# M709X.net
KiCad netlist of a schematic drawn in EAGLE
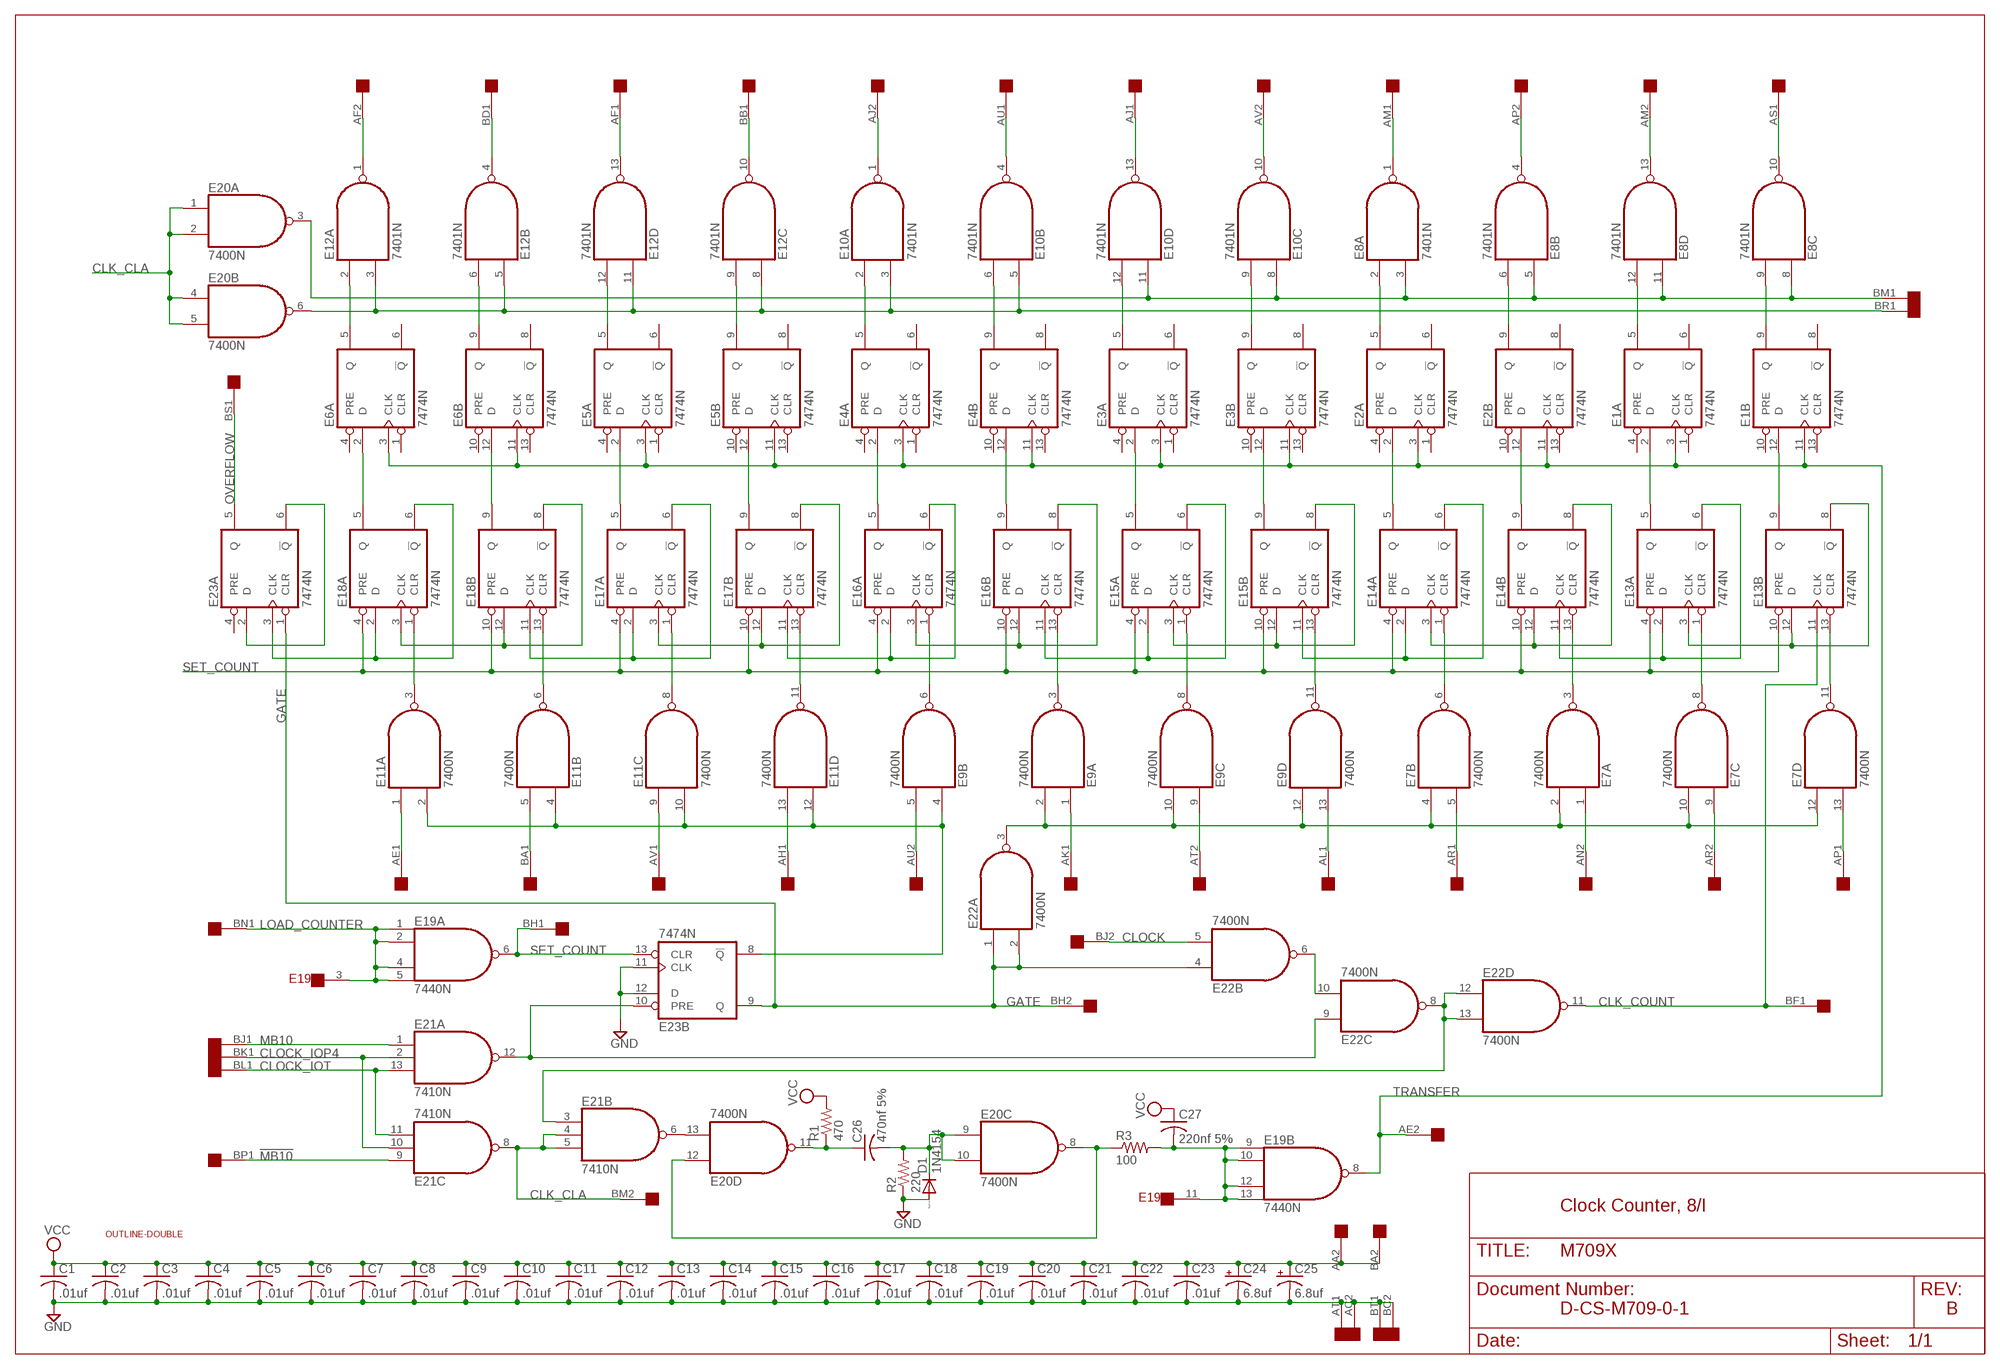
[diagram p0: schematic, sheet 1]

(export (version "E")
  (design (tool "Eeschema 10.0.6"))
  (components
    (comp (ref "C1")
      (value ".01uf")
      (footprint "eagle-import:C075-032X103")
      (libsource (lib "eagle-import") (part "C-US075-032X103"))
    )
    (comp (ref "C2")
      (value ".01uf")
      (footprint "eagle-import:C075-032X103")
      (libsource (lib "eagle-import") (part "C-US075-032X103"))
    )
    (comp (ref "C3")
      (value ".01uf")
      (footprint "eagle-import:C075-032X103")
      (libsource (lib "eagle-import") (part "C-US075-032X103"))
    )
    (comp (ref "C4")
      (value ".01uf")
      (footprint "eagle-import:C075-032X103")
      (libsource (lib "eagle-import") (part "C-US075-032X103"))
    )
    (comp (ref "C5")
      (value ".01uf")
      (footprint "eagle-import:C075-032X103")
      (libsource (lib "eagle-import") (part "C-US075-032X103"))
    )
    (comp (ref "C6")
      (value ".01uf")
      (footprint "eagle-import:C075-032X103")
      (libsource (lib "eagle-import") (part "C-US075-032X103"))
    )
    (comp (ref "C7")
      (value ".01uf")
      (footprint "eagle-import:C075-032X103")
      (libsource (lib "eagle-import") (part "C-US075-032X103"))
    )
    (comp (ref "C8")
      (value ".01uf")
      (footprint "eagle-import:C075-032X103")
      (libsource (lib "eagle-import") (part "C-US075-032X103"))
    )
    (comp (ref "C9")
      (value ".01uf")
      (footprint "eagle-import:C075-032X103")
      (libsource (lib "eagle-import") (part "C-US075-032X103"))
    )
    (comp (ref "C10")
      (value ".01uf")
      (footprint "eagle-import:C075-032X103")
      (libsource (lib "eagle-import") (part "C-US075-032X103"))
    )
    (comp (ref "C11")
      (value ".01uf")
      (footprint "eagle-import:C075-032X103")
      (libsource (lib "eagle-import") (part "C-US075-032X103"))
    )
    (comp (ref "C12")
      (value ".01uf")
      (footprint "eagle-import:C075-032X103")
      (libsource (lib "eagle-import") (part "C-US075-032X103"))
    )
    (comp (ref "C13")
      (value ".01uf")
      (footprint "eagle-import:C075-032X103")
      (libsource (lib "eagle-import") (part "C-US075-032X103"))
    )
    (comp (ref "C14")
      (value ".01uf")
      (footprint "eagle-import:C075-032X103")
      (libsource (lib "eagle-import") (part "C-US075-032X103"))
    )
    (comp (ref "C15")
      (value ".01uf")
      (footprint "eagle-import:C075-032X103")
      (libsource (lib "eagle-import") (part "C-US075-032X103"))
    )
    (comp (ref "C16")
      (value ".01uf")
      (footprint "eagle-import:C075-032X103")
      (libsource (lib "eagle-import") (part "C-US075-032X103"))
    )
    (comp (ref "C17")
      (value ".01uf")
      (footprint "eagle-import:C075-032X103")
      (libsource (lib "eagle-import") (part "C-US075-032X103"))
    )
    (comp (ref "C18")
      (value ".01uf")
      (footprint "eagle-import:C075-032X103")
      (libsource (lib "eagle-import") (part "C-US075-032X103"))
    )
    (comp (ref "C19")
      (value ".01uf")
      (footprint "eagle-import:C075-032X103")
      (libsource (lib "eagle-import") (part "C-US075-032X103"))
    )
    (comp (ref "C20")
      (value ".01uf")
      (footprint "eagle-import:C075-032X103")
      (libsource (lib "eagle-import") (part "C-US075-032X103"))
    )
    (comp (ref "C21")
      (value ".01uf")
      (footprint "eagle-import:C075-032X103")
      (libsource (lib "eagle-import") (part "C-US075-032X103"))
    )
    (comp (ref "C22")
      (value ".01uf")
      (footprint "eagle-import:C075-032X103")
      (libsource (lib "eagle-import") (part "C-US075-032X103"))
    )
    (comp (ref "C23")
      (value ".01uf")
      (footprint "eagle-import:C075-032X103")
      (libsource (lib "eagle-import") (part "C-US075-032X103"))
    )
    (comp (ref "C24")
      (value "6.8uf")
      (footprint "eagle-import:E15-5")
      (libsource (lib "eagle-import") (part "CPOL-USE15-5AXIAL"))
    )
    (comp (ref "C25")
      (value "6.8uf")
      (footprint "eagle-import:E15-5")
      (libsource (lib "eagle-import") (part "CPOL-USE15-5AXIAL"))
    )
    (comp (ref "C26")
      (value "470nf 5%")
      (footprint "eagle-import:C075-032X103")
      (libsource (lib "eagle-import") (part "C-US075-032X103"))
    )
    (comp (ref "C27")
      (value "220nf 5%")
      (footprint "eagle-import:C075-032X103")
      (libsource (lib "eagle-import") (part "C-US075-032X103"))
    )
    (comp (ref "D1")
      (value "1N4154")
      (footprint "eagle-import:SOD61B")
      (libsource (lib "eagle-import") (part "DIODE-SOD61B"))
    )
    (comp (ref "E1")
      (value "7474N")
      (footprint "eagle-import:DIL14")
      (libsource (lib "eagle-import") (part "7474NS"))
    )
    (comp (ref "E2")
      (value "7474N")
      (footprint "eagle-import:DIL14")
      (libsource (lib "eagle-import") (part "7474NS"))
    )
    (comp (ref "E3")
      (value "7474N")
      (footprint "eagle-import:DIL14")
      (libsource (lib "eagle-import") (part "7474NS"))
    )
    (comp (ref "E4")
      (value "7474N")
      (footprint "eagle-import:DIL14")
      (libsource (lib "eagle-import") (part "7474NS"))
    )
    (comp (ref "E5")
      (value "7474N")
      (footprint "eagle-import:DIL14")
      (libsource (lib "eagle-import") (part "7474NS"))
    )
    (comp (ref "E6")
      (value "7474N")
      (footprint "eagle-import:DIL14")
      (libsource (lib "eagle-import") (part "7474NS"))
    )
    (comp (ref "E7")
      (value "7400N")
      (footprint "eagle-import:DIL14")
      (libsource (lib "eagle-import") (part "7400N"))
    )
    (comp (ref "E8")
      (value "7401N")
      (footprint "eagle-import:DIL14")
      (libsource (lib "eagle-import") (part "7401NLS"))
    )
    (comp (ref "E9")
      (value "7400N")
      (footprint "eagle-import:DIL14")
      (libsource (lib "eagle-import") (part "7400N"))
    )
    (comp (ref "E10")
      (value "7401N")
      (footprint "eagle-import:DIL14")
      (libsource (lib "eagle-import") (part "7401NLS"))
    )
    (comp (ref "E11")
      (value "7400N")
      (footprint "eagle-import:DIL14")
      (libsource (lib "eagle-import") (part "7400N"))
    )
    (comp (ref "E12")
      (value "7401N")
      (footprint "eagle-import:DIL14")
      (libsource (lib "eagle-import") (part "7401NLS"))
    )
    (comp (ref "E13")
      (value "7474N")
      (footprint "eagle-import:DIL14")
      (libsource (lib "eagle-import") (part "7474NS"))
    )
    (comp (ref "E14")
      (value "7474N")
      (footprint "eagle-import:DIL14")
      (libsource (lib "eagle-import") (part "7474NS"))
    )
    (comp (ref "E15")
      (value "7474N")
      (footprint "eagle-import:DIL14")
      (libsource (lib "eagle-import") (part "7474NS"))
    )
    (comp (ref "E16")
      (value "7474N")
      (footprint "eagle-import:DIL14")
      (libsource (lib "eagle-import") (part "7474NS"))
    )
    (comp (ref "E17")
      (value "7474N")
      (footprint "eagle-import:DIL14")
      (libsource (lib "eagle-import") (part "7474NS"))
    )
    (comp (ref "E18")
      (value "7474N")
      (footprint "eagle-import:DIL14")
      (libsource (lib "eagle-import") (part "7474NS"))
    )
    (comp (ref "E19")
      (value "7440N")
      (footprint "eagle-import:DIL14")
      (libsource (lib "eagle-import") (part "7440NS"))
    )
    (comp (ref "E20")
      (value "7400N")
      (footprint "eagle-import:DIL14")
      (libsource (lib "eagle-import") (part "7400N"))
    )
    (comp (ref "E21")
      (value "7410N")
      (footprint "eagle-import:DIL14")
      (libsource (lib "eagle-import") (part "7410N"))
    )
    (comp (ref "E22")
      (value "7400N")
      (footprint "eagle-import:DIL14")
      (libsource (lib "eagle-import") (part "7400N"))
    )
    (comp (ref "E23")
      (value "7474N")
      (footprint "eagle-import:DIL14")
      (libsource (lib "eagle-import") (part "7474NS"))
    )
    (comp (ref "R1")
      (value "470")
      (footprint "eagle-import:0207_15")
      (libsource (lib "eagle-import") (part "R-US_0207/15"))
    )
    (comp (ref "R2")
      (value "220")
      (footprint "eagle-import:0207_15")
      (libsource (lib "eagle-import") (part "R-US_0207/15"))
    )
    (comp (ref "R3")
      (value "100")
      (footprint "eagle-import:0207_15")
      (libsource (lib "eagle-import") (part "R-US_0207/15"))
    )
    (comp (ref "U$1")
      (value "OUTLINE-DOUBLE")
      (footprint "eagle-import:DOUBLE")
      (libsource (lib "eagle-import") (part "OUTLINE-DOUBLE"))
    )
    (comp (ref "U$2")
      (value "DOUBLE")
      (footprint "eagle-import:EDGE-CON4")
      (libsource (lib "eagle-import") (part "DOUBLE"))
    )
  )
  (nets
    (net (code "1") (name "/CLK_CLA") (class "Default")
      (node (ref "E20") (pin "1") (pinfunction "I0_1") (pintype "input"))
      (node (ref "E20") (pin "2") (pinfunction "I1_2") (pintype "input"))
      (node (ref "E20") (pin "4") (pinfunction "I0_4") (pintype "input"))
      (node (ref "E20") (pin "5") (pinfunction "I1_5") (pintype "input"))
      (node (ref "E21") (pin "4") (pinfunction "I1_4") (pintype "input"))
      (node (ref "E21") (pin "5") (pinfunction "I2_5") (pintype "input"))
      (node (ref "E21") (pin "8") (pinfunction "O_8") (pintype "output"))
      (node (ref "U$2") (pin "BM2") (pinfunction "1_BM2") (pintype "bidirectional"))
    )
    (net (code "2") (name "/CLK_COUNT") (class "Default")
      (node (ref "E13") (pin "11") (pinfunction "CLK_11") (pintype "input"))
      (node (ref "E22") (pin "11") (pinfunction "O_11") (pintype "output"))
      (node (ref "U$2") (pin "BF1") (pinfunction "1_BF1") (pintype "bidirectional"))
    )
    (net (code "3") (name "/CLOCK") (class "Default")
      (node (ref "E22") (pin "5") (pinfunction "I1_5") (pintype "input"))
      (node (ref "U$2") (pin "BJ2") (pinfunction "1_BJ2") (pintype "bidirectional"))
    )
    (net (code "4") (name "/CLOCK_IOP4") (class "Default")
      (node (ref "E21") (pin "10") (pinfunction "I1_10") (pintype "input"))
      (node (ref "E21") (pin "2") (pinfunction "I1_2") (pintype "input"))
      (node (ref "U$2") (pin "BK1") (pinfunction "1_BK1") (pintype "bidirectional"))
    )
    (net (code "5") (name "/CLOCK_IOT") (class "Default")
      (node (ref "E21") (pin "11") (pinfunction "I2_11") (pintype "input"))
      (node (ref "E21") (pin "13") (pinfunction "I2_13") (pintype "input"))
      (node (ref "U$2") (pin "BL1") (pinfunction "1_BL1") (pintype "bidirectional"))
    )
    (net (code "6") (name "/GATE") (class "Default")
      (node (ref "E22") (pin "1") (pinfunction "I0_1") (pintype "input"))
      (node (ref "E22") (pin "2") (pinfunction "I1_2") (pintype "input"))
      (node (ref "E22") (pin "4") (pinfunction "I0_4") (pintype "input"))
      (node (ref "E23") (pin "1") (pinfunction "CLR_1") (pintype "input"))
      (node (ref "E23") (pin "9") (pinfunction "Q_9") (pintype "output"))
      (node (ref "U$2") (pin "BH2") (pinfunction "1_BH2") (pintype "bidirectional"))
    )
    (net (code "7") (name "/LOAD_COUNTER") (class "Default")
      (node (ref "E19") (pin "1") (pinfunction "I0_1") (pintype "input"))
      (node (ref "E19") (pin "2") (pinfunction "I1_2") (pintype "input"))
      (node (ref "E19") (pin "3") (pinfunction "NC_3") (pintype "passive"))
      (node (ref "E19") (pin "4") (pinfunction "I2_4") (pintype "input"))
      (node (ref "E19") (pin "5") (pinfunction "I3_5") (pintype "input"))
      (node (ref "U$2") (pin "BN1") (pinfunction "1_BN1") (pintype "bidirectional"))
    )
    (net (code "8") (name "/MB10") (class "Default")
      (node (ref "E21") (pin "1") (pinfunction "I0_1") (pintype "input"))
      (node (ref "U$2") (pin "BJ1") (pinfunction "1_BJ1") (pintype "bidirectional"))
    )
    (net (code "9") (name "/OVERFLOW") (class "Default")
      (node (ref "E23") (pin "5") (pinfunction "Q_5") (pintype "output"))
      (node (ref "U$2") (pin "BS1") (pinfunction "1_BS1") (pintype "bidirectional"))
    )
    (net (code "10") (name "/SET_COUNT") (class "Default")
      (node (ref "E13") (pin "10") (pinfunction "PRE_10") (pintype "input"))
      (node (ref "E13") (pin "4") (pinfunction "PRE_4") (pintype "input"))
      (node (ref "E14") (pin "10") (pinfunction "PRE_10") (pintype "input"))
      (node (ref "E14") (pin "4") (pinfunction "PRE_4") (pintype "input"))
      (node (ref "E15") (pin "10") (pinfunction "PRE_10") (pintype "input"))
      (node (ref "E15") (pin "4") (pinfunction "PRE_4") (pintype "input"))
      (node (ref "E16") (pin "10") (pinfunction "PRE_10") (pintype "input"))
      (node (ref "E16") (pin "4") (pinfunction "PRE_4") (pintype "input"))
      (node (ref "E17") (pin "10") (pinfunction "PRE_10") (pintype "input"))
      (node (ref "E17") (pin "4") (pinfunction "PRE_4") (pintype "input"))
      (node (ref "E18") (pin "10") (pinfunction "PRE_10") (pintype "input"))
      (node (ref "E18") (pin "4") (pinfunction "PRE_4") (pintype "input"))
      (node (ref "E19") (pin "6") (pinfunction "O_6") (pintype "output"))
      (node (ref "E23") (pin "13") (pinfunction "CLR_13") (pintype "input"))
      (node (ref "U$2") (pin "BH1") (pinfunction "1_BH1") (pintype "bidirectional"))
    )
    (net (code "11") (name "/TRANSFER") (class "Default")
      (node (ref "E1") (pin "11") (pinfunction "CLK_11") (pintype "input"))
      (node (ref "E1") (pin "3") (pinfunction "CLK_3") (pintype "input"))
      (node (ref "E19") (pin "8") (pinfunction "O_8") (pintype "output"))
      (node (ref "E2") (pin "11") (pinfunction "CLK_11") (pintype "input"))
      (node (ref "E2") (pin "3") (pinfunction "CLK_3") (pintype "input"))
      (node (ref "E3") (pin "11") (pinfunction "CLK_11") (pintype "input"))
      (node (ref "E3") (pin "3") (pinfunction "CLK_3") (pintype "input"))
      (node (ref "E4") (pin "11") (pinfunction "CLK_11") (pintype "input"))
      (node (ref "E4") (pin "3") (pinfunction "CLK_3") (pintype "input"))
      (node (ref "E5") (pin "11") (pinfunction "CLK_11") (pintype "input"))
      (node (ref "E5") (pin "3") (pinfunction "CLK_3") (pintype "input"))
      (node (ref "E6") (pin "11") (pinfunction "CLK_11") (pintype "input"))
      (node (ref "E6") (pin "3") (pinfunction "CLK_3") (pintype "input"))
      (node (ref "U$2") (pin "AE2") (pinfunction "1_AE2") (pintype "bidirectional"))
    )
    (net (code "12") (name "/~{MB10}") (class "Default")
      (node (ref "E21") (pin "9") (pinfunction "I0_9") (pintype "input"))
      (node (ref "U$2") (pin "BP1") (pinfunction "1_BP1") (pintype "bidirectional"))
    )
    (net (code "13") (name "GND") (class "Default")
      (node (ref "C1") (pin "2") (pinfunction "2_2") (pintype "passive"))
      (node (ref "C10") (pin "2") (pinfunction "2_2") (pintype "passive"))
      (node (ref "C11") (pin "2") (pinfunction "2_2") (pintype "passive"))
      (node (ref "C12") (pin "2") (pinfunction "2_2") (pintype "passive"))
      (node (ref "C13") (pin "2") (pinfunction "2_2") (pintype "passive"))
      (node (ref "C14") (pin "2") (pinfunction "2_2") (pintype "passive"))
      (node (ref "C15") (pin "2") (pinfunction "2_2") (pintype "passive"))
      (node (ref "C16") (pin "2") (pinfunction "2_2") (pintype "passive"))
      (node (ref "C17") (pin "2") (pinfunction "2_2") (pintype "passive"))
      (node (ref "C18") (pin "2") (pinfunction "2_2") (pintype "passive"))
      (node (ref "C19") (pin "2") (pinfunction "2_2") (pintype "passive"))
      (node (ref "C2") (pin "2") (pinfunction "2_2") (pintype "passive"))
      (node (ref "C20") (pin "2") (pinfunction "2_2") (pintype "passive"))
      (node (ref "C21") (pin "2") (pinfunction "2_2") (pintype "passive"))
      (node (ref "C22") (pin "2") (pinfunction "2_2") (pintype "passive"))
      (node (ref "C23") (pin "2") (pinfunction "2_2") (pintype "passive"))
      (node (ref "C24") (pin "-") (pinfunction "-_-") (pintype "passive"))
      (node (ref "C25") (pin "-") (pinfunction "-_-") (pintype "passive"))
      (node (ref "C3") (pin "2") (pinfunction "2_2") (pintype "passive"))
      (node (ref "C4") (pin "2") (pinfunction "2_2") (pintype "passive"))
      (node (ref "C5") (pin "2") (pinfunction "2_2") (pintype "passive"))
      (node (ref "C6") (pin "2") (pinfunction "2_2") (pintype "passive"))
      (node (ref "C7") (pin "2") (pinfunction "2_2") (pintype "passive"))
      (node (ref "C8") (pin "2") (pinfunction "2_2") (pintype "passive"))
      (node (ref "C9") (pin "2") (pinfunction "2_2") (pintype "passive"))
      (node (ref "D1") (pin "A") (pinfunction "A_A") (pintype "passive"))
      (node (ref "E23") (pin "11") (pinfunction "CLK_11") (pintype "input"))
      (node (ref "E23") (pin "12") (pinfunction "D_12") (pintype "input"))
      (node (ref "R2") (pin "1") (pinfunction "1_1") (pintype "passive"))
      (node (ref "U$2") (pin "AC2") (pinfunction "1_AC2") (pintype "bidirectional"))
      (node (ref "U$2") (pin "AT1") (pinfunction "1_AT1") (pintype "bidirectional"))
      (node (ref "U$2") (pin "BC2") (pinfunction "1_BC2") (pintype "bidirectional"))
      (node (ref "U$2") (pin "BT1") (pinfunction "1_BT1") (pintype "bidirectional"))
    )
    (net (code "14") (name "Net-(E1A-Q)") (class "Default")
      (node (ref "E1") (pin "5") (pinfunction "Q_5") (pintype "output"))
      (node (ref "E8") (pin "12") (pinfunction "I1_12") (pintype "input"))
    )
    (net (code "15") (name "Net-(E1B-Q)") (class "Default")
      (node (ref "E1") (pin "9") (pinfunction "Q_9") (pintype "output"))
      (node (ref "E8") (pin "9") (pinfunction "I1_9") (pintype "input"))
    )
    (net (code "16") (name "Net-(E2A-Q)") (class "Default")
      (node (ref "E2") (pin "5") (pinfunction "Q_5") (pintype "output"))
      (node (ref "E8") (pin "2") (pinfunction "I0_2") (pintype "input"))
    )
    (net (code "17") (name "Net-(E2B-Q)") (class "Default")
      (node (ref "E2") (pin "9") (pinfunction "Q_9") (pintype "output"))
      (node (ref "E8") (pin "6") (pinfunction "I1_6") (pintype "input"))
    )
    (net (code "18") (name "Net-(E7A-I0)") (class "Default")
      (node (ref "E7") (pin "1") (pinfunction "I0_1") (pintype "input"))
      (node (ref "U$2") (pin "AN2") (pinfunction "1_AN2") (pintype "bidirectional"))
    )
    (net (code "19") (name "Net-(E7B-I1)") (class "Default")
      (node (ref "E7") (pin "5") (pinfunction "I1_5") (pintype "input"))
      (node (ref "U$2") (pin "AR1") (pinfunction "1_AR1") (pintype "bidirectional"))
    )
    (net (code "20") (name "Net-(E7C-I0)") (class "Default")
      (node (ref "E7") (pin "9") (pinfunction "I0_9") (pintype "input"))
      (node (ref "U$2") (pin "AR2") (pinfunction "1_AR2") (pintype "bidirectional"))
    )
    (net (code "21") (name "Net-(E7D-I1)") (class "Default")
      (node (ref "E7") (pin "13") (pinfunction "I1_13") (pintype "input"))
      (node (ref "U$2") (pin "AP1") (pinfunction "1_AP1") (pintype "bidirectional"))
    )
    (net (code "22") (name "Net-(E8A-O)") (class "Default")
      (node (ref "E8") (pin "1") (pinfunction "O_1") (pintype "open_collector"))
      (node (ref "U$2") (pin "AM1") (pinfunction "1_AM1") (pintype "bidirectional"))
    )
    (net (code "23") (name "Net-(E8B-O)") (class "Default")
      (node (ref "E8") (pin "4") (pinfunction "O_4") (pintype "open_collector"))
      (node (ref "U$2") (pin "AP2") (pinfunction "1_AP2") (pintype "bidirectional"))
    )
    (net (code "24") (name "Net-(E8C-O)") (class "Default")
      (node (ref "E8") (pin "10") (pinfunction "O_10") (pintype "open_collector"))
      (node (ref "U$2") (pin "AS1") (pinfunction "1_AS1") (pintype "bidirectional"))
    )
    (net (code "25") (name "Net-(E8D-O)") (class "Default")
      (node (ref "E8") (pin "13") (pinfunction "O_13") (pintype "open_collector"))
      (node (ref "U$2") (pin "AM2") (pinfunction "1_AM2") (pintype "bidirectional"))
    )
    (net (code "26") (name "Net-(E9A-I0)") (class "Default")
      (node (ref "E9") (pin "1") (pinfunction "I0_1") (pintype "input"))
      (node (ref "U$2") (pin "AK1") (pinfunction "1_AK1") (pintype "bidirectional"))
    )
    (net (code "27") (name "Net-(E9B-I1)") (class "Default")
      (node (ref "E9") (pin "5") (pinfunction "I1_5") (pintype "input"))
      (node (ref "U$2") (pin "AU2") (pinfunction "1_AU2") (pintype "bidirectional"))
    )
    (net (code "28") (name "Net-(E9C-I0)") (class "Default")
      (node (ref "E9") (pin "9") (pinfunction "I0_9") (pintype "input"))
      (node (ref "U$2") (pin "AT2") (pinfunction "1_AT2") (pintype "bidirectional"))
    )
    (net (code "29") (name "Net-(E9D-I1)") (class "Default")
      (node (ref "E9") (pin "13") (pinfunction "I1_13") (pintype "input"))
      (node (ref "U$2") (pin "AL1") (pinfunction "1_AL1") (pintype "bidirectional"))
    )
    (net (code "30") (name "Net-(E10A-I0)") (class "Default")
      (node (ref "E10") (pin "2") (pinfunction "I0_2") (pintype "input"))
      (node (ref "E4") (pin "5") (pinfunction "Q_5") (pintype "output"))
    )
    (net (code "31") (name "Net-(E10A-I1)") (class "Default")
      (node (ref "E10") (pin "3") (pinfunction "I1_3") (pintype "input"))
      (node (ref "E10") (pin "5") (pinfunction "I0_5") (pintype "input"))
      (node (ref "E12") (pin "11") (pinfunction "I0_11") (pintype "input"))
      (node (ref "E12") (pin "3") (pinfunction "I1_3") (pintype "input"))
      (node (ref "E12") (pin "5") (pinfunction "I0_5") (pintype "input"))
      (node (ref "E12") (pin "8") (pinfunction "I0_8") (pintype "input"))
      (node (ref "E20") (pin "6") (pinfunction "O_6") (pintype "output"))
      (node (ref "U$2") (pin "BR1") (pinfunction "1_BR1") (pintype "bidirectional"))
    )
    (net (code "32") (name "Net-(E10A-O)") (class "Default")
      (node (ref "E10") (pin "1") (pinfunction "O_1") (pintype "open_collector"))
      (node (ref "U$2") (pin "AJ2") (pinfunction "1_AJ2") (pintype "bidirectional"))
    )
    (net (code "33") (name "Net-(E10B-I1)") (class "Default")
      (node (ref "E10") (pin "6") (pinfunction "I1_6") (pintype "input"))
      (node (ref "E4") (pin "9") (pinfunction "Q_9") (pintype "output"))
    )
    (net (code "34") (name "Net-(E10B-O)") (class "Default")
      (node (ref "E10") (pin "4") (pinfunction "O_4") (pintype "open_collector"))
      (node (ref "U$2") (pin "AU1") (pinfunction "1_AU1") (pintype "bidirectional"))
    )
    (net (code "35") (name "Net-(E10C-I0)") (class "Default")
      (node (ref "E10") (pin "11") (pinfunction "I0_11") (pintype "input"))
      (node (ref "E10") (pin "8") (pinfunction "I0_8") (pintype "input"))
      (node (ref "E20") (pin "3") (pinfunction "O_3") (pintype "output"))
      (node (ref "E8") (pin "11") (pinfunction "I0_11") (pintype "input"))
      (node (ref "E8") (pin "3") (pinfunction "I1_3") (pintype "input"))
      (node (ref "E8") (pin "5") (pinfunction "I0_5") (pintype "input"))
      (node (ref "E8") (pin "8") (pinfunction "I0_8") (pintype "input"))
      (node (ref "U$2") (pin "BM1") (pinfunction "1_BM1") (pintype "bidirectional"))
    )
    (net (code "36") (name "Net-(E10C-I1)") (class "Default")
      (node (ref "E10") (pin "9") (pinfunction "I1_9") (pintype "input"))
      (node (ref "E3") (pin "9") (pinfunction "Q_9") (pintype "output"))
    )
    (net (code "37") (name "Net-(E10C-O)") (class "Default")
      (node (ref "E10") (pin "10") (pinfunction "O_10") (pintype "open_collector"))
      (node (ref "U$2") (pin "AV2") (pinfunction "1_AV2") (pintype "bidirectional"))
    )
    (net (code "38") (name "Net-(E10D-I1)") (class "Default")
      (node (ref "E10") (pin "12") (pinfunction "I1_12") (pintype "input"))
      (node (ref "E3") (pin "5") (pinfunction "Q_5") (pintype "output"))
    )
    (net (code "39") (name "Net-(E10D-O)") (class "Default")
      (node (ref "E10") (pin "13") (pinfunction "O_13") (pintype "open_collector"))
      (node (ref "U$2") (pin "AJ1") (pinfunction "1_AJ1") (pintype "bidirectional"))
    )
    (net (code "40") (name "Net-(E11A-I0)") (class "Default")
      (node (ref "E11") (pin "1") (pinfunction "I0_1") (pintype "input"))
      (node (ref "U$2") (pin "AE1") (pinfunction "1_AE1") (pintype "bidirectional"))
    )
    (net (code "41") (name "Net-(E11A-I1)") (class "Default")
      (node (ref "E11") (pin "10") (pinfunction "I1_10") (pintype "input"))
      (node (ref "E11") (pin "12") (pinfunction "I0_12") (pintype "input"))
      (node (ref "E11") (pin "2") (pinfunction "I1_2") (pintype "input"))
      (node (ref "E11") (pin "4") (pinfunction "I0_4") (pintype "input"))
      (node (ref "E23") (pin "8") (pinfunction "~{Q}_8") (pintype "output"))
      (node (ref "E9") (pin "4") (pinfunction "I0_4") (pintype "input"))
    )
    (net (code "42") (name "Net-(E11A-O)") (class "Default")
      (node (ref "E11") (pin "3") (pinfunction "O_3") (pintype "output"))
      (node (ref "E18") (pin "1") (pinfunction "CLR_1") (pintype "input"))
    )
    (net (code "43") (name "Net-(E11B-I1)") (class "Default")
      (node (ref "E11") (pin "5") (pinfunction "I1_5") (pintype "input"))
      (node (ref "U$2") (pin "BA1") (pinfunction "1_BA1") (pintype "bidirectional"))
    )
    (net (code "44") (name "Net-(E11B-O)") (class "Default")
      (node (ref "E11") (pin "6") (pinfunction "O_6") (pintype "output"))
      (node (ref "E18") (pin "13") (pinfunction "CLR_13") (pintype "input"))
    )
    (net (code "45") (name "Net-(E11C-I0)") (class "Default")
      (node (ref "E11") (pin "9") (pinfunction "I0_9") (pintype "input"))
      (node (ref "U$2") (pin "AV1") (pinfunction "1_AV1") (pintype "bidirectional"))
    )
    (net (code "46") (name "Net-(E11C-O)") (class "Default")
      (node (ref "E11") (pin "8") (pinfunction "O_8") (pintype "output"))
      (node (ref "E17") (pin "1") (pinfunction "CLR_1") (pintype "input"))
    )
    (net (code "47") (name "Net-(E11D-I1)") (class "Default")
      (node (ref "E11") (pin "13") (pinfunction "I1_13") (pintype "input"))
      (node (ref "U$2") (pin "AH1") (pinfunction "1_AH1") (pintype "bidirectional"))
    )
    (net (code "48") (name "Net-(E11D-O)") (class "Default")
      (node (ref "E11") (pin "11") (pinfunction "O_11") (pintype "output"))
      (node (ref "E17") (pin "13") (pinfunction "CLR_13") (pintype "input"))
    )
    (net (code "49") (name "Net-(E12A-I0)") (class "Default")
      (node (ref "E12") (pin "2") (pinfunction "I0_2") (pintype "input"))
      (node (ref "E6") (pin "5") (pinfunction "Q_5") (pintype "output"))
    )
    (net (code "50") (name "Net-(E12A-O)") (class "Default")
      (node (ref "E12") (pin "1") (pinfunction "O_1") (pintype "open_collector"))
      (node (ref "U$2") (pin "AF2") (pinfunction "1_AF2") (pintype "bidirectional"))
    )
    (net (code "51") (name "Net-(E12B-I1)") (class "Default")
      (node (ref "E12") (pin "6") (pinfunction "I1_6") (pintype "input"))
      (node (ref "E6") (pin "9") (pinfunction "Q_9") (pintype "output"))
    )
    (net (code "52") (name "Net-(E12B-O)") (class "Default")
      (node (ref "E12") (pin "4") (pinfunction "O_4") (pintype "open_collector"))
      (node (ref "U$2") (pin "BD1") (pinfunction "1_BD1") (pintype "bidirectional"))
    )
    (net (code "53") (name "Net-(E12C-I1)") (class "Default")
      (node (ref "E12") (pin "9") (pinfunction "I1_9") (pintype "input"))
      (node (ref "E5") (pin "9") (pinfunction "Q_9") (pintype "output"))
    )
    (net (code "54") (name "Net-(E12C-O)") (class "Default")
      (node (ref "E12") (pin "10") (pinfunction "O_10") (pintype "open_collector"))
      (node (ref "U$2") (pin "BB1") (pinfunction "1_BB1") (pintype "bidirectional"))
    )
    (net (code "55") (name "Net-(E12D-I1)") (class "Default")
      (node (ref "E12") (pin "12") (pinfunction "I1_12") (pintype "input"))
      (node (ref "E5") (pin "5") (pinfunction "Q_5") (pintype "output"))
    )
    (net (code "56") (name "Net-(E12D-O)") (class "Default")
      (node (ref "E12") (pin "13") (pinfunction "O_13") (pintype "open_collector"))
      (node (ref "U$2") (pin "AF1") (pinfunction "1_AF1") (pintype "bidirectional"))
    )
    (net (code "57") (name "Net-(E13A-CLK)") (class "Default")
      (node (ref "E13") (pin "12") (pinfunction "D_12") (pintype "input"))
      (node (ref "E13") (pin "3") (pinfunction "CLK_3") (pintype "input"))
      (node (ref "E13") (pin "8") (pinfunction "~{Q}_8") (pintype "output"))
    )
    (net (code "58") (name "Net-(E13A-CLR)") (class "Default")
      (node (ref "E13") (pin "1") (pinfunction "CLR_1") (pintype "input"))
      (node (ref "E7") (pin "8") (pinfunction "O_8") (pintype "output"))
    )
    (net (code "59") (name "Net-(E13A-D)") (class "Default")
      (node (ref "E13") (pin "2") (pinfunction "D_2") (pintype "input"))
      (node (ref "E13") (pin "6") (pinfunction "~{Q}_6") (pintype "output"))
      (node (ref "E14") (pin "11") (pinfunction "CLK_11") (pintype "input"))
    )
    (net (code "60") (name "Net-(E13A-Q)") (class "Default")
      (node (ref "E1") (pin "2") (pinfunction "D_2") (pintype "input"))
      (node (ref "E13") (pin "5") (pinfunction "Q_5") (pintype "output"))
    )
    (net (code "61") (name "Net-(E13B-CLR)") (class "Default")
      (node (ref "E13") (pin "13") (pinfunction "CLR_13") (pintype "input"))
      (node (ref "E7") (pin "11") (pinfunction "O_11") (pintype "output"))
    )
    (net (code "62") (name "Net-(E13B-Q)") (class "Default")
      (node (ref "E1") (pin "12") (pinfunction "D_12") (pintype "input"))
      (node (ref "E13") (pin "9") (pinfunction "Q_9") (pintype "output"))
    )
    (net (code "63") (name "Net-(E14A-CLK)") (class "Default")
      (node (ref "E14") (pin "12") (pinfunction "D_12") (pintype "input"))
      (node (ref "E14") (pin "3") (pinfunction "CLK_3") (pintype "input"))
      (node (ref "E14") (pin "8") (pinfunction "~{Q}_8") (pintype "output"))
    )
    (net (code "64") (name "Net-(E14A-CLR)") (class "Default")
      (node (ref "E14") (pin "1") (pinfunction "CLR_1") (pintype "input"))
      (node (ref "E7") (pin "6") (pinfunction "O_6") (pintype "output"))
    )
    (net (code "65") (name "Net-(E14A-D)") (class "Default")
      (node (ref "E14") (pin "2") (pinfunction "D_2") (pintype "input"))
      (node (ref "E14") (pin "6") (pinfunction "~{Q}_6") (pintype "output"))
      (node (ref "E15") (pin "11") (pinfunction "CLK_11") (pintype "input"))
    )
    (net (code "66") (name "Net-(E14A-Q)") (class "Default")
      (node (ref "E14") (pin "5") (pinfunction "Q_5") (pintype "output"))
      (node (ref "E2") (pin "2") (pinfunction "D_2") (pintype "input"))
    )
    (net (code "67") (name "Net-(E14B-CLR)") (class "Default")
      (node (ref "E14") (pin "13") (pinfunction "CLR_13") (pintype "input"))
      (node (ref "E7") (pin "3") (pinfunction "O_3") (pintype "output"))
    )
    (net (code "68") (name "Net-(E14B-Q)") (class "Default")
      (node (ref "E14") (pin "9") (pinfunction "Q_9") (pintype "output"))
      (node (ref "E2") (pin "12") (pinfunction "D_12") (pintype "input"))
    )
    (net (code "69") (name "Net-(E15A-CLK)") (class "Default")
      (node (ref "E15") (pin "12") (pinfunction "D_12") (pintype "input"))
      (node (ref "E15") (pin "3") (pinfunction "CLK_3") (pintype "input"))
      (node (ref "E15") (pin "8") (pinfunction "~{Q}_8") (pintype "output"))
    )
    (net (code "70") (name "Net-(E15A-CLR)") (class "Default")
      (node (ref "E15") (pin "1") (pinfunction "CLR_1") (pintype "input"))
      (node (ref "E9") (pin "8") (pinfunction "O_8") (pintype "output"))
    )
    (net (code "71") (name "Net-(E15A-D)") (class "Default")
      (node (ref "E15") (pin "2") (pinfunction "D_2") (pintype "input"))
      (node (ref "E15") (pin "6") (pinfunction "~{Q}_6") (pintype "output"))
      (node (ref "E16") (pin "11") (pinfunction "CLK_11") (pintype "input"))
    )
    (net (code "72") (name "Net-(E15A-Q)") (class "Default")
      (node (ref "E15") (pin "5") (pinfunction "Q_5") (pintype "output"))
      (node (ref "E3") (pin "2") (pinfunction "D_2") (pintype "input"))
    )
    (net (code "73") (name "Net-(E15B-CLR)") (class "Default")
      (node (ref "E15") (pin "13") (pinfunction "CLR_13") (pintype "input"))
      (node (ref "E9") (pin "11") (pinfunction "O_11") (pintype "output"))
    )
    (net (code "74") (name "Net-(E15B-Q)") (class "Default")
      (node (ref "E15") (pin "9") (pinfunction "Q_9") (pintype "output"))
      (node (ref "E3") (pin "12") (pinfunction "D_12") (pintype "input"))
    )
    (net (code "75") (name "Net-(E16A-CLK)") (class "Default")
      (node (ref "E16") (pin "12") (pinfunction "D_12") (pintype "input"))
      (node (ref "E16") (pin "3") (pinfunction "CLK_3") (pintype "input"))
      (node (ref "E16") (pin "8") (pinfunction "~{Q}_8") (pintype "output"))
    )
    (net (code "76") (name "Net-(E16A-CLR)") (class "Default")
      (node (ref "E16") (pin "1") (pinfunction "CLR_1") (pintype "input"))
      (node (ref "E9") (pin "6") (pinfunction "O_6") (pintype "output"))
    )
    (net (code "77") (name "Net-(E16A-D)") (class "Default")
      (node (ref "E16") (pin "2") (pinfunction "D_2") (pintype "input"))
      (node (ref "E16") (pin "6") (pinfunction "~{Q}_6") (pintype "output"))
      (node (ref "E17") (pin "11") (pinfunction "CLK_11") (pintype "input"))
    )
    (net (code "78") (name "Net-(E16A-Q)") (class "Default")
      (node (ref "E16") (pin "5") (pinfunction "Q_5") (pintype "output"))
      (node (ref "E4") (pin "2") (pinfunction "D_2") (pintype "input"))
    )
    (net (code "79") (name "Net-(E16B-CLR)") (class "Default")
      (node (ref "E16") (pin "13") (pinfunction "CLR_13") (pintype "input"))
      (node (ref "E9") (pin "3") (pinfunction "O_3") (pintype "output"))
    )
    (net (code "80") (name "Net-(E16B-Q)") (class "Default")
      (node (ref "E16") (pin "9") (pinfunction "Q_9") (pintype "output"))
      (node (ref "E4") (pin "12") (pinfunction "D_12") (pintype "input"))
    )
    (net (code "81") (name "Net-(E17A-CLK)") (class "Default")
      (node (ref "E17") (pin "12") (pinfunction "D_12") (pintype "input"))
      (node (ref "E17") (pin "3") (pinfunction "CLK_3") (pintype "input"))
      (node (ref "E17") (pin "8") (pinfunction "~{Q}_8") (pintype "output"))
    )
    (net (code "82") (name "Net-(E17A-D)") (class "Default")
      (node (ref "E17") (pin "2") (pinfunction "D_2") (pintype "input"))
      (node (ref "E17") (pin "6") (pinfunction "~{Q}_6") (pintype "output"))
      (node (ref "E18") (pin "11") (pinfunction "CLK_11") (pintype "input"))
    )
    (net (code "83") (name "Net-(E17A-Q)") (class "Default")
      (node (ref "E17") (pin "5") (pinfunction "Q_5") (pintype "output"))
      (node (ref "E5") (pin "2") (pinfunction "D_2") (pintype "input"))
    )
    (net (code "84") (name "Net-(E17B-Q)") (class "Default")
      (node (ref "E17") (pin "9") (pinfunction "Q_9") (pintype "output"))
      (node (ref "E5") (pin "12") (pinfunction "D_12") (pintype "input"))
    )
    (net (code "85") (name "Net-(E18A-CLK)") (class "Default")
      (node (ref "E18") (pin "12") (pinfunction "D_12") (pintype "input"))
      (node (ref "E18") (pin "3") (pinfunction "CLK_3") (pintype "input"))
      (node (ref "E18") (pin "8") (pinfunction "~{Q}_8") (pintype "output"))
    )
    (net (code "86") (name "Net-(E18A-D)") (class "Default")
      (node (ref "E18") (pin "2") (pinfunction "D_2") (pintype "input"))
      (node (ref "E18") (pin "6") (pinfunction "~{Q}_6") (pintype "output"))
      (node (ref "E23") (pin "3") (pinfunction "CLK_3") (pintype "input"))
    )
    (net (code "87") (name "Net-(E18A-Q)") (class "Default")
      (node (ref "E18") (pin "5") (pinfunction "Q_5") (pintype "output"))
      (node (ref "E6") (pin "2") (pinfunction "D_2") (pintype "input"))
    )
    (net (code "88") (name "Net-(E18B-Q)") (class "Default")
      (node (ref "E18") (pin "9") (pinfunction "Q_9") (pintype "output"))
      (node (ref "E6") (pin "12") (pinfunction "D_12") (pintype "input"))
    )
    (net (code "89") (name "Net-(E19A-NC)") (class "Default")
      (node (ref "C27") (pin "2") (pinfunction "2_2") (pintype "passive"))
      (node (ref "E19") (pin "10") (pinfunction "I1_10") (pintype "input"))
      (node (ref "E19") (pin "11") (pinfunction "NC_11") (pintype "passive"))
      (node (ref "E19") (pin "12") (pinfunction "I2_12") (pintype "input"))
      (node (ref "E19") (pin "13") (pinfunction "I3_13") (pintype "input"))
      (node (ref "E19") (pin "9") (pinfunction "I0_9") (pintype "input"))
      (node (ref "R3") (pin "2") (pinfunction "2_2") (pintype "passive"))
    )
    (net (code "90") (name "Net-(E20C-I0)") (class "Default")
      (node (ref "C26") (pin "2") (pinfunction "2_2") (pintype "passive"))
      (node (ref "D1") (pin "C") (pinfunction "C_C") (pintype "passive"))
      (node (ref "E20") (pin "10") (pinfunction "I1_10") (pintype "input"))
      (node (ref "E20") (pin "9") (pinfunction "I0_9") (pintype "input"))
      (node (ref "R2") (pin "2") (pinfunction "2_2") (pintype "passive"))
    )
    (net (code "91") (name "Net-(E20C-O)") (class "Default")
      (node (ref "E20") (pin "12") (pinfunction "I0_12") (pintype "input"))
      (node (ref "E20") (pin "8") (pinfunction "O_8") (pintype "output"))
      (node (ref "R3") (pin "1") (pinfunction "1_1") (pintype "passive"))
    )
    (net (code "92") (name "Net-(E20D-I1)") (class "Default")
      (node (ref "E20") (pin "13") (pinfunction "I1_13") (pintype "input"))
      (node (ref "E21") (pin "6") (pinfunction "O_6") (pintype "output"))
    )
    (net (code "93") (name "Net-(E20D-O)") (class "Default")
      (node (ref "C26") (pin "1") (pinfunction "1_1") (pintype "passive"))
      (node (ref "E20") (pin "11") (pinfunction "O_11") (pintype "output"))
      (node (ref "R1") (pin "1") (pinfunction "1_1") (pintype "passive"))
    )
    (net (code "94") (name "Net-(E21A-O)") (class "Default")
      (node (ref "E21") (pin "12") (pinfunction "O_12") (pintype "output"))
      (node (ref "E22") (pin "9") (pinfunction "I0_9") (pintype "input"))
      (node (ref "E23") (pin "10") (pinfunction "PRE_10") (pintype "input"))
    )
    (net (code "95") (name "Net-(E21B-I0)") (class "Default")
      (node (ref "E21") (pin "3") (pinfunction "I0_3") (pintype "input"))
      (node (ref "E22") (pin "12") (pinfunction "I0_12") (pintype "input"))
      (node (ref "E22") (pin "13") (pinfunction "I1_13") (pintype "input"))
      (node (ref "E22") (pin "8") (pinfunction "O_8") (pintype "output"))
    )
    (net (code "96") (name "Net-(E22A-O)") (class "Default")
      (node (ref "E22") (pin "3") (pinfunction "O_3") (pintype "output"))
      (node (ref "E7") (pin "10") (pinfunction "I1_10") (pintype "input"))
      (node (ref "E7") (pin "12") (pinfunction "I0_12") (pintype "input"))
      (node (ref "E7") (pin "2") (pinfunction "I1_2") (pintype "input"))
      (node (ref "E7") (pin "4") (pinfunction "I0_4") (pintype "input"))
      (node (ref "E9") (pin "10") (pinfunction "I1_10") (pintype "input"))
      (node (ref "E9") (pin "12") (pinfunction "I0_12") (pintype "input"))
      (node (ref "E9") (pin "2") (pinfunction "I1_2") (pintype "input"))
    )
    (net (code "97") (name "Net-(E22B-O)") (class "Default")
      (node (ref "E22") (pin "10") (pinfunction "I1_10") (pintype "input"))
      (node (ref "E22") (pin "6") (pinfunction "O_6") (pintype "output"))
    )
    (net (code "98") (name "Net-(E23A-D)") (class "Default")
      (node (ref "E23") (pin "2") (pinfunction "D_2") (pintype "input"))
      (node (ref "E23") (pin "6") (pinfunction "~{Q}_6") (pintype "output"))
    )
    (net (code "99") (name "VCC") (class "Default")
      (node (ref "C1") (pin "1") (pinfunction "1_1") (pintype "passive"))
      (node (ref "C10") (pin "1") (pinfunction "1_1") (pintype "passive"))
      (node (ref "C11") (pin "1") (pinfunction "1_1") (pintype "passive"))
      (node (ref "C12") (pin "1") (pinfunction "1_1") (pintype "passive"))
      (node (ref "C13") (pin "1") (pinfunction "1_1") (pintype "passive"))
      (node (ref "C14") (pin "1") (pinfunction "1_1") (pintype "passive"))
      (node (ref "C15") (pin "1") (pinfunction "1_1") (pintype "passive"))
      (node (ref "C16") (pin "1") (pinfunction "1_1") (pintype "passive"))
      (node (ref "C17") (pin "1") (pinfunction "1_1") (pintype "passive"))
      (node (ref "C18") (pin "1") (pinfunction "1_1") (pintype "passive"))
      (node (ref "C19") (pin "1") (pinfunction "1_1") (pintype "passive"))
      (node (ref "C2") (pin "1") (pinfunction "1_1") (pintype "passive"))
      (node (ref "C20") (pin "1") (pinfunction "1_1") (pintype "passive"))
      (node (ref "C21") (pin "1") (pinfunction "1_1") (pintype "passive"))
      (node (ref "C22") (pin "1") (pinfunction "1_1") (pintype "passive"))
      (node (ref "C23") (pin "1") (pinfunction "1_1") (pintype "passive"))
      (node (ref "C24") (pin "+") (pinfunction "+_+") (pintype "passive"))
      (node (ref "C25") (pin "+") (pinfunction "+_+") (pintype "passive"))
      (node (ref "C27") (pin "1") (pinfunction "1_1") (pintype "passive"))
      (node (ref "C3") (pin "1") (pinfunction "1_1") (pintype "passive"))
      (node (ref "C4") (pin "1") (pinfunction "1_1") (pintype "passive"))
      (node (ref "C5") (pin "1") (pinfunction "1_1") (pintype "passive"))
      (node (ref "C6") (pin "1") (pinfunction "1_1") (pintype "passive"))
      (node (ref "C7") (pin "1") (pinfunction "1_1") (pintype "passive"))
      (node (ref "C8") (pin "1") (pinfunction "1_1") (pintype "passive"))
      (node (ref "C9") (pin "1") (pinfunction "1_1") (pintype "passive"))
      (node (ref "R1") (pin "2") (pinfunction "2_2") (pintype "passive"))
      (node (ref "U$2") (pin "AA2") (pinfunction "1_AA2") (pintype "bidirectional"))
      (node (ref "U$2") (pin "BA2") (pinfunction "1_BA2") (pintype "bidirectional"))
    )
    (net (code "100") (name "unconnected-(E1A-CLR-Pad1)") (class "Default")
      (node (ref "E1") (pin "1") (pinfunction "CLR_1") (pintype "input"))
    )
    (net (code "101") (name "unconnected-(E1A-PRE-Pad4)") (class "Default")
      (node (ref "E1") (pin "4") (pinfunction "PRE_4") (pintype "input"))
    )
    (net (code "102") (name "unconnected-(E1A-~{Q}-Pad6)") (class "Default")
      (node (ref "E1") (pin "6") (pinfunction "~{Q}_6") (pintype "output"))
    )
    (net (code "103") (name "unconnected-(E1B-CLR-Pad13)") (class "Default")
      (node (ref "E1") (pin "13") (pinfunction "CLR_13") (pintype "input"))
    )
    (net (code "104") (name "unconnected-(E1B-PRE-Pad10)") (class "Default")
      (node (ref "E1") (pin "10") (pinfunction "PRE_10") (pintype "input"))
    )
    (net (code "105") (name "unconnected-(E1B-~{Q}-Pad8)") (class "Default")
      (node (ref "E1") (pin "8") (pinfunction "~{Q}_8") (pintype "output"))
    )
    (net (code "106") (name "unconnected-(E2A-CLR-Pad1)") (class "Default")
      (node (ref "E2") (pin "1") (pinfunction "CLR_1") (pintype "input"))
    )
    (net (code "107") (name "unconnected-(E2A-PRE-Pad4)") (class "Default")
      (node (ref "E2") (pin "4") (pinfunction "PRE_4") (pintype "input"))
    )
    (net (code "108") (name "unconnected-(E2A-~{Q}-Pad6)") (class "Default")
      (node (ref "E2") (pin "6") (pinfunction "~{Q}_6") (pintype "output"))
    )
    (net (code "109") (name "unconnected-(E2B-CLR-Pad13)") (class "Default")
      (node (ref "E2") (pin "13") (pinfunction "CLR_13") (pintype "input"))
    )
    (net (code "110") (name "unconnected-(E2B-PRE-Pad10)") (class "Default")
      (node (ref "E2") (pin "10") (pinfunction "PRE_10") (pintype "input"))
    )
    (net (code "111") (name "unconnected-(E2B-~{Q}-Pad8)") (class "Default")
      (node (ref "E2") (pin "8") (pinfunction "~{Q}_8") (pintype "output"))
    )
    (net (code "112") (name "unconnected-(E3A-CLR-Pad1)") (class "Default")
      (node (ref "E3") (pin "1") (pinfunction "CLR_1") (pintype "input"))
    )
    (net (code "113") (name "unconnected-(E3A-PRE-Pad4)") (class "Default")
      (node (ref "E3") (pin "4") (pinfunction "PRE_4") (pintype "input"))
    )
    (net (code "114") (name "unconnected-(E3A-~{Q}-Pad6)") (class "Default")
      (node (ref "E3") (pin "6") (pinfunction "~{Q}_6") (pintype "output"))
    )
    (net (code "115") (name "unconnected-(E3B-CLR-Pad13)") (class "Default")
      (node (ref "E3") (pin "13") (pinfunction "CLR_13") (pintype "input"))
    )
    (net (code "116") (name "unconnected-(E3B-PRE-Pad10)") (class "Default")
      (node (ref "E3") (pin "10") (pinfunction "PRE_10") (pintype "input"))
    )
    (net (code "117") (name "unconnected-(E3B-~{Q}-Pad8)") (class "Default")
      (node (ref "E3") (pin "8") (pinfunction "~{Q}_8") (pintype "output"))
    )
    (net (code "118") (name "unconnected-(E4A-CLR-Pad1)") (class "Default")
      (node (ref "E4") (pin "1") (pinfunction "CLR_1") (pintype "input"))
    )
    (net (code "119") (name "unconnected-(E4A-PRE-Pad4)") (class "Default")
      (node (ref "E4") (pin "4") (pinfunction "PRE_4") (pintype "input"))
    )
    (net (code "120") (name "unconnected-(E4A-~{Q}-Pad6)") (class "Default")
      (node (ref "E4") (pin "6") (pinfunction "~{Q}_6") (pintype "output"))
    )
    (net (code "121") (name "unconnected-(E4B-CLR-Pad13)") (class "Default")
      (node (ref "E4") (pin "13") (pinfunction "CLR_13") (pintype "input"))
    )
    (net (code "122") (name "unconnected-(E4B-PRE-Pad10)") (class "Default")
      (node (ref "E4") (pin "10") (pinfunction "PRE_10") (pintype "input"))
    )
    (net (code "123") (name "unconnected-(E4B-~{Q}-Pad8)") (class "Default")
      (node (ref "E4") (pin "8") (pinfunction "~{Q}_8") (pintype "output"))
    )
    (net (code "124") (name "unconnected-(E5A-CLR-Pad1)") (class "Default")
      (node (ref "E5") (pin "1") (pinfunction "CLR_1") (pintype "input"))
    )
    (net (code "125") (name "unconnected-(E5A-PRE-Pad4)") (class "Default")
      (node (ref "E5") (pin "4") (pinfunction "PRE_4") (pintype "input"))
    )
    (net (code "126") (name "unconnected-(E5A-~{Q}-Pad6)") (class "Default")
      (node (ref "E5") (pin "6") (pinfunction "~{Q}_6") (pintype "output"))
    )
    (net (code "127") (name "unconnected-(E5B-CLR-Pad13)") (class "Default")
      (node (ref "E5") (pin "13") (pinfunction "CLR_13") (pintype "input"))
    )
    (net (code "128") (name "unconnected-(E5B-PRE-Pad10)") (class "Default")
      (node (ref "E5") (pin "10") (pinfunction "PRE_10") (pintype "input"))
    )
    (net (code "129") (name "unconnected-(E5B-~{Q}-Pad8)") (class "Default")
      (node (ref "E5") (pin "8") (pinfunction "~{Q}_8") (pintype "output"))
    )
    (net (code "130") (name "unconnected-(E6A-CLR-Pad1)") (class "Default")
      (node (ref "E6") (pin "1") (pinfunction "CLR_1") (pintype "input"))
    )
    (net (code "131") (name "unconnected-(E6A-PRE-Pad4)") (class "Default")
      (node (ref "E6") (pin "4") (pinfunction "PRE_4") (pintype "input"))
    )
    (net (code "132") (name "unconnected-(E6A-~{Q}-Pad6)") (class "Default")
      (node (ref "E6") (pin "6") (pinfunction "~{Q}_6") (pintype "output"))
    )
    (net (code "133") (name "unconnected-(E6B-CLR-Pad13)") (class "Default")
      (node (ref "E6") (pin "13") (pinfunction "CLR_13") (pintype "input"))
    )
    (net (code "134") (name "unconnected-(E6B-PRE-Pad10)") (class "Default")
      (node (ref "E6") (pin "10") (pinfunction "PRE_10") (pintype "input"))
    )
    (net (code "135") (name "unconnected-(E6B-~{Q}-Pad8)") (class "Default")
      (node (ref "E6") (pin "8") (pinfunction "~{Q}_8") (pintype "output"))
    )
    (net (code "136") (name "unconnected-(E23A-PRE-Pad4)") (class "Default")
      (node (ref "E23") (pin "4") (pinfunction "PRE_4") (pintype "input"))
    )
  )
)
